# ra-02com.net
KiCad netlist of a schematic drawn in Altium Designer
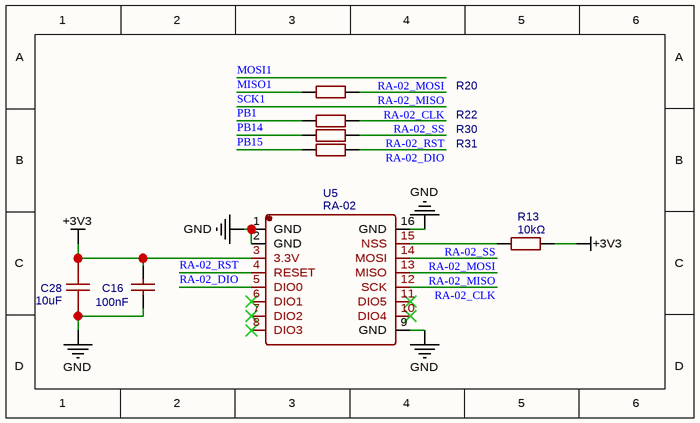
[diagram p0: ra-02com.schdoc]

(export (version "E")
  (design (tool "Eeschema 10.0.6"))
  (components
    (comp (ref "C16")
      (value "100nF")
      (fields
        (field (name "MANUFACTURER PART") "CL05B104KO5NNNC")
        (field (name "MANUFACTURER") "SAMSUNG(三星)")
      )
      (libsource (lib "altium-import") (part "root_3_100nF_"))
    )
    (comp (ref "C28")
      (value "10uF")
      (fields
        (field (name "MANUFACTURER") "SAMSUNG(三星)")
        (field (name "MANUFACTURER PART") "CL10A106MA8NRNC")
      )
      (libsource (lib "altium-import") (part "root_3_10uF_"))
    )
    (comp (ref "R13")
      (value "10kΩ")
      (fields
        (field (name "MANUFACTURER") "UNI-ROYAL(厚声)")
        (field (name "MANUFACTURER PART") "0402WGF1002TCE")
      )
      (libsource (lib "altium-import") (part "root_0_10kΩ_"))
    )
    (comp (ref "R20")
      (value "22Ω")
      (fields
        (field (name "MANUFACTURER") "UNI-ROYAL(厚声)")
        (field (name "MANUFACTURER PART") "0402WGF220JTCE")
      )
      (libsource (lib "altium-import") (part "root_0_22Ω_"))
    )
    (comp (ref "R22")
      (value "22Ω")
      (fields
        (field (name "MANUFACTURER") "UNI-ROYAL(厚声)")
        (field (name "MANUFACTURER PART") "0402WGF220JTCE")
      )
      (libsource (lib "altium-import") (part "root_0_22Ω_"))
    )
    (comp (ref "R30")
      (value "22Ω")
      (fields
        (field (name "MANUFACTURER") "UNI-ROYAL(厚声)")
        (field (name "MANUFACTURER PART") "0402WGF220JTCE")
      )
      (libsource (lib "altium-import") (part "root_0_22Ω_"))
    )
    (comp (ref "R31")
      (value "22Ω")
      (fields
        (field (name "MANUFACTURER") "UNI-ROYAL(厚声)")
        (field (name "MANUFACTURER PART") "0402WGF220JTCE")
      )
      (libsource (lib "altium-import") (part "root_0_22Ω_"))
    )
    (comp (ref "U5")
      (value "RA-02")
      (fields
        (field (name "MANUFACTURER") "Ai-Thinker(安信可)")
        (field (name "MANUFACTURER PART") "Ra-02")
        (field (name "CONTRIBUTOR") "LCSC")
      )
      (libsource (lib "altium-import") (part "root_0_RA-02_"))
    )
  )
  (nets
    (net (code "1") (name "+3V3") (class "Default")
      (node (ref "C16") (pin "2") (pinfunction "2_2") (pintype "passive"))
      (node (ref "C28") (pin "1") (pinfunction "1_1") (pintype "passive"))
      (node (ref "R13") (pin "2") (pinfunction "2_2") (pintype "passive"))
      (node (ref "U5") (pin "3") (pinfunction "3.3V_3") (pintype "passive"))
    )
    (net (code "2") (name "/MISO1") (class "Default")
      (node (ref "R20") (pin "1") (pinfunction "1_1") (pintype "passive"))
    )
    (net (code "3") (name "/MOSI1") (class "Default")
      (node (ref "U5") (pin "14") (pinfunction "MOSI_14") (pintype "passive"))
    )
    (net (code "4") (name "/PB1") (class "Default")
      (node (ref "R22") (pin "1") (pinfunction "1_1") (pintype "passive"))
    )
    (net (code "5") (name "/PB14") (class "Default")
      (node (ref "R30") (pin "1") (pinfunction "1_1") (pintype "passive"))
    )
    (net (code "6") (name "/PB15") (class "Default")
      (node (ref "R31") (pin "1") (pinfunction "1_1") (pintype "passive"))
    )
    (net (code "7") (name "/RA-02_CLK") (class "Default")
      (node (ref "U5") (pin "12") (pinfunction "SCK_12") (pintype "passive"))
    )
    (net (code "8") (name "/RA-02_DIO") (class "Default")
      (node (ref "R31") (pin "2") (pinfunction "2_2") (pintype "passive"))
      (node (ref "U5") (pin "5") (pinfunction "DIO0_5") (pintype "passive"))
    )
    (net (code "9") (name "/RA-02_MISO") (class "Default")
      (node (ref "R20") (pin "2") (pinfunction "2_2") (pintype "passive"))
      (node (ref "U5") (pin "13") (pinfunction "MISO_13") (pintype "passive"))
    )
    (net (code "10") (name "/RA-02_RST") (class "Default")
      (node (ref "R30") (pin "2") (pinfunction "2_2") (pintype "passive"))
      (node (ref "U5") (pin "4") (pinfunction "RESET_4") (pintype "passive"))
    )
    (net (code "11") (name "/RA-02_SS") (class "Default")
      (node (ref "R13") (pin "1") (pinfunction "1_1") (pintype "passive"))
      (node (ref "R22") (pin "2") (pinfunction "2_2") (pintype "passive"))
      (node (ref "U5") (pin "15") (pinfunction "NSS_15") (pintype "passive"))
    )
    (net (code "12") (name "GND") (class "Default")
      (node (ref "C16") (pin "1") (pinfunction "1_1") (pintype "passive"))
      (node (ref "C28") (pin "2") (pinfunction "2_2") (pintype "passive"))
      (node (ref "U5") (pin "1") (pinfunction "GND_1") (pintype "passive"))
      (node (ref "U5") (pin "16") (pinfunction "GND_16") (pintype "passive"))
      (node (ref "U5") (pin "2") (pinfunction "GND_2") (pintype "passive"))
      (node (ref "U5") (pin "9") (pinfunction "GND_9") (pintype "passive"))
    )
    (net (code "13") (name "unconnected-(U5-DIO1-Pad6)") (class "Default")
      (node (ref "U5") (pin "6") (pinfunction "DIO1_6") (pintype "passive+no_connect"))
    )
    (net (code "14") (name "unconnected-(U5-DIO2-Pad7)") (class "Default")
      (node (ref "U5") (pin "7") (pinfunction "DIO2_7") (pintype "passive+no_connect"))
    )
    (net (code "15") (name "unconnected-(U5-DIO3-Pad8)") (class "Default")
      (node (ref "U5") (pin "8") (pinfunction "DIO3_8") (pintype "passive+no_connect"))
    )
    (net (code "16") (name "unconnected-(U5-DIO4-Pad10)") (class "Default")
      (node (ref "U5") (pin "10") (pinfunction "DIO4_10") (pintype "passive+no_connect"))
    )
    (net (code "17") (name "unconnected-(U5-DIO5-Pad11)") (class "Default")
      (node (ref "U5") (pin "11") (pinfunction "DIO5_11") (pintype "passive+no_connect"))
    )
  )
)
